# usb_sheet.net
KiCad netlist of a schematic drawn in Altium Designer
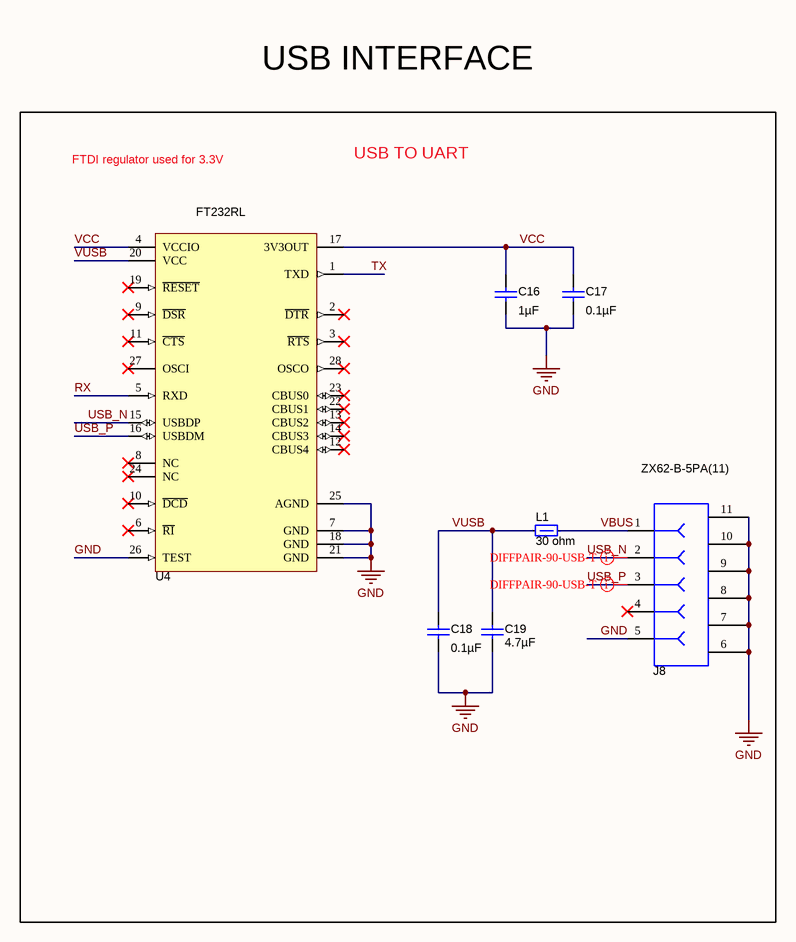
[diagram p0: usb sheet.SchDoc]

(export (version "E")
  (design (tool "Eeschema 10.0.6"))
  (components
    (comp (ref "C16")
      (value "GRM155R61A105KE15D")
      (footprint "0402L")
      (description "CAP, CERM, 1 µF, 10 V, +/- 10%, X5R, 0402")
      (fields
        (field (name "MANUFACTURER") "MuRata")
        (field (name "VALUEDISPLAYED") "1µF")
        (field (name "PUBLISHER") "Texas Instruments")
      )
      (libsource (lib "drvs-motor") (part "GRM155R61A105KE15D"))
    )
    (comp (ref "C17")
      (value "GRM155R61A104KA01D")
      (footprint "0402L")
      (description "CAP, CERM, 0.1 µF, 10 V, +/- 10%, X5R, 0402")
      (fields
        (field (name "MANUFACTURER") "MuRata")
        (field (name "VALUEDISPLAYED") "0.1µF")
        (field (name "PUBLISHER") "Texas Instruments")
      )
      (libsource (lib "drvs-motor") (part "GRM155R61A104KA01D"))
    )
    (comp (ref "C18")
      (value "GRM155R61A104KA01D")
      (footprint "0402L")
      (description "CAP, CERM, 0.1 µF, 10 V, +/- 10%, X5R, 0402")
      (fields
        (field (name "MANUFACTURER") "MuRata")
        (field (name "VALUEDISPLAYED") "0.1µF")
        (field (name "PUBLISHER") "Texas Instruments")
      )
      (libsource (lib "drvs-motor") (part "GRM155R61A104KA01D"))
    )
    (comp (ref "C19")
      (value "CGB3B1X5R1A475K055AC")
      (footprint "0603L")
      (description "CAP, CERM, 4.7 µF, 10 V, +/- 10%, X5R, 0603")
      (fields
        (field (name "MANUFACTURER") "TDK")
        (field (name "VALUEDISPLAYED") "4.7µF")
        (field (name "PUBLISHER") "Texas Instruments")
      )
      (libsource (lib "drvs-motor") (part "CGB3B1X5R1A475K055AC"))
    )
    (comp (ref "J8")
      (value "ZX62-B-5PA(11)")
      (footprint "CONN_USB_micro_ZX62-B-5PA")
      (description "Connector, Receptacle, Micro-USB Type B, R/A, Bottom Mount SMT")
      (fields
        (field (name "MANUFACTURER") "Hirose Electric Co. Ltd.")
        (field (name "SYMBOLCREATOR") "a0411947")
        (field (name "PUBLISHER") "Texas Instruments")
      )
      (libsource (lib "drvs-motor") (part "ZX62-B-5PA(11)"))
    )
    (comp (ref "L1")
      (value "30 ohm")
      (footprint "0805L")
      (description "Ferrite Bead, 30 ohm @ 100 MHz, 1.5 A, 0805")
      (fields
        (field (name "MANUFACTURER") "TDK")
        (field (name "PARTNUMBER") "MMZ2012R300A")
        (field (name "PUBLISHER") "Texas Instruments")
      )
      (libsource (lib "drvs-motor") (part "MMZ2012R300A_2"))
    )
    (comp (ref "U4")
      (value "FT232RL")
      (footprint "SSOP28_M")
      (description "USB to Serial UART, SSOP28")
      (fields
        (field (name "MANUFACTURER") "FTDI")
        (field (name "SYMBOLCREATOR") "x0208326")
        (field (name "PUBLISHER") "Texas Instruments")
      )
      (libsource (lib "drvs-motor") (part "FT232RL"))
    )
  )
  (nets
    (net (code "1") (name "/RX") (class "Default")
      (node (ref "U4") (pin "5") (pinfunction "RXD_5") (pintype "input"))
    )
    (net (code "2") (name "/TX") (class "Default")
      (node (ref "U4") (pin "1") (pinfunction "TXD_1") (pintype "output"))
    )
    (net (code "3") (name "/USB_N") (class "Default")
      (node (ref "J8") (pin "2") (pinfunction "2_2") (pintype "passive"))
      (node (ref "U4") (pin "15") (pinfunction "USBDP_15") (pintype "bidirectional"))
    )
    (net (code "4") (name "/USB_P") (class "Default")
      (node (ref "J8") (pin "3") (pinfunction "3_3") (pintype "passive"))
      (node (ref "U4") (pin "16") (pinfunction "USBDM_16") (pintype "bidirectional"))
    )
    (net (code "5") (name "/VBUS") (class "Default")
      (node (ref "J8") (pin "1") (pinfunction "1_1") (pintype "passive"))
      (node (ref "L1") (pin "2") (pinfunction "2_2") (pintype "passive"))
    )
    (net (code "6") (name "/VCC") (class "Default")
      (node (ref "C16") (pin "1") (pinfunction "1_1") (pintype "passive"))
      (node (ref "C17") (pin "1") (pinfunction "1_1") (pintype "passive"))
      (node (ref "U4") (pin "17") (pinfunction "3V3OUT_17") (pintype "power_in"))
      (node (ref "U4") (pin "4") (pinfunction "VCCIO_4") (pintype "power_in"))
    )
    (net (code "7") (name "/VUSB") (class "Default")
      (node (ref "C18") (pin "1") (pinfunction "1_1") (pintype "passive"))
      (node (ref "C19") (pin "1") (pinfunction "1_1") (pintype "passive"))
      (node (ref "L1") (pin "1") (pinfunction "1_1") (pintype "passive"))
      (node (ref "U4") (pin "20") (pinfunction "VCC_20") (pintype "power_in"))
    )
    (net (code "8") (name "GND") (class "Default")
      (node (ref "C16") (pin "2") (pinfunction "2_2") (pintype "passive"))
      (node (ref "C17") (pin "2") (pinfunction "2_2") (pintype "passive"))
      (node (ref "C18") (pin "2") (pinfunction "2_2") (pintype "passive"))
      (node (ref "C19") (pin "2") (pinfunction "2_2") (pintype "passive"))
      (node (ref "J8") (pin "10") (pinfunction "10_10") (pintype "passive"))
      (node (ref "J8") (pin "11") (pinfunction "11_11") (pintype "passive"))
      (node (ref "J8") (pin "5") (pinfunction "5_5") (pintype "passive"))
      (node (ref "J8") (pin "6") (pinfunction "6_6") (pintype "passive"))
      (node (ref "J8") (pin "7") (pinfunction "7_7") (pintype "passive"))
      (node (ref "J8") (pin "8") (pinfunction "8_8") (pintype "passive"))
      (node (ref "J8") (pin "9") (pinfunction "9_9") (pintype "passive"))
      (node (ref "U4") (pin "18") (pinfunction "GND_18") (pintype "power_in"))
      (node (ref "U4") (pin "21") (pinfunction "GND_21") (pintype "power_in"))
      (node (ref "U4") (pin "25") (pinfunction "AGND_25") (pintype "power_in"))
      (node (ref "U4") (pin "26") (pinfunction "TEST_26") (pintype "input"))
      (node (ref "U4") (pin "7") (pinfunction "GND_7") (pintype "power_in"))
    )
    (net (code "9") (name "unconnected-(J8-Pad4)") (class "Default")
      (node (ref "J8") (pin "4") (pinfunction "4_4") (pintype "passive+no_connect"))
    )
    (net (code "10") (name "unconnected-(U4-CBUS0-Pad23)") (class "Default")
      (node (ref "U4") (pin "23") (pinfunction "CBUS0_23") (pintype "bidirectional+no_connect"))
    )
    (net (code "11") (name "unconnected-(U4-CBUS1-Pad22)") (class "Default")
      (node (ref "U4") (pin "22") (pinfunction "CBUS1_22") (pintype "bidirectional+no_connect"))
    )
    (net (code "12") (name "unconnected-(U4-CBUS2-Pad13)") (class "Default")
      (node (ref "U4") (pin "13") (pinfunction "CBUS2_13") (pintype "bidirectional+no_connect"))
    )
    (net (code "13") (name "unconnected-(U4-CBUS3-Pad14)") (class "Default")
      (node (ref "U4") (pin "14") (pinfunction "CBUS3_14") (pintype "bidirectional+no_connect"))
    )
    (net (code "14") (name "unconnected-(U4-CBUS4-Pad12)") (class "Default")
      (node (ref "U4") (pin "12") (pinfunction "CBUS4_12") (pintype "bidirectional+no_connect"))
    )
    (net (code "15") (name "unconnected-(U4-CTS-Pad11)") (class "Default")
      (node (ref "U4") (pin "11") (pinfunction "CTS_11") (pintype "input+no_connect"))
    )
    (net (code "16") (name "unconnected-(U4-DCD-Pad10)") (class "Default")
      (node (ref "U4") (pin "10") (pinfunction "DCD_10") (pintype "input+no_connect"))
    )
    (net (code "17") (name "unconnected-(U4-DSR-Pad9)") (class "Default")
      (node (ref "U4") (pin "9") (pinfunction "DSR_9") (pintype "input+no_connect"))
    )
    (net (code "18") (name "unconnected-(U4-DTR-Pad2)") (class "Default")
      (node (ref "U4") (pin "2") (pinfunction "DTR_2") (pintype "output+no_connect"))
    )
    (net (code "19") (name "unconnected-(U4-NC-Pad8)") (class "Default")
      (node (ref "U4") (pin "8") (pinfunction "NC_8") (pintype "passive+no_connect"))
    )
    (net (code "20") (name "unconnected-(U4-NC-Pad24)") (class "Default")
      (node (ref "U4") (pin "24") (pinfunction "NC_24") (pintype "passive+no_connect"))
    )
    (net (code "21") (name "unconnected-(U4-OSCI-Pad27)") (class "Default")
      (node (ref "U4") (pin "27") (pinfunction "OSCI_27") (pintype "passive+no_connect"))
    )
    (net (code "22") (name "unconnected-(U4-OSCO-Pad28)") (class "Default")
      (node (ref "U4") (pin "28") (pinfunction "OSCO_28") (pintype "output+no_connect"))
    )
    (net (code "23") (name "unconnected-(U4-RESET-Pad19)") (class "Default")
      (node (ref "U4") (pin "19") (pinfunction "RESET_19") (pintype "input+no_connect"))
    )
    (net (code "24") (name "unconnected-(U4-RI-Pad6)") (class "Default")
      (node (ref "U4") (pin "6") (pinfunction "RI_6") (pintype "input+no_connect"))
    )
    (net (code "25") (name "unconnected-(U4-RTS-Pad3)") (class "Default")
      (node (ref "U4") (pin "3") (pinfunction "RTS_3") (pintype "output+no_connect"))
    )
  )
)
